# gpio_expander.net
KiCad netlist of a schematic drawn in Altium Designer
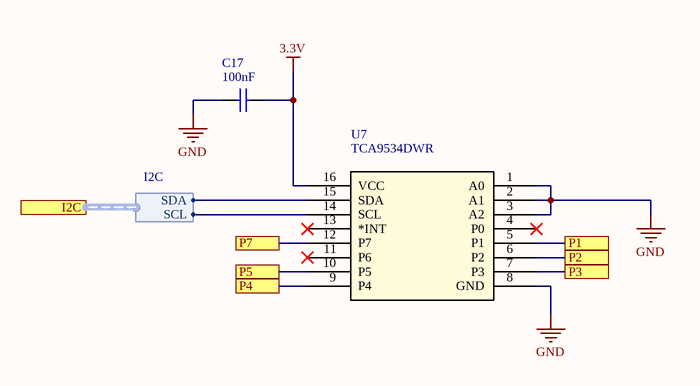
[diagram p0: gpio_expander.SchDoc]

(export (version "E")
  (design (tool "Eeschema 10.0.6"))
  (components
    (comp (ref "C17")
      (value "100nF")
      (footprint "0603 - Capacitor")
      (description "Nonpolarized Capacitor")
      (fields (field (name "Comment") "Capacitor - Nonpolarized"))
      (libsource (lib "General") (part "Capacitor - Nonpolarized"))
    )
    (comp (ref "U7")
      (value "TCA9534DWR")
      (footprint "TCA9534DWR")
      (fields (field (name "COPYRIGHT") "Copyright (C) 2022 Ultra Librarian. All rights reserved."))
      (libsource (lib "General") (part "TCA9534DWR"))
    )
  )
  (nets
    (net (code "2") (name "/P1") (class "Default")
      (node (ref "U7") (pin "5") (pinfunction "P1_5") (pintype "passive"))
    )
    (net (code "3") (name "/P2") (class "Default")
      (node (ref "U7") (pin "6") (pinfunction "P2_6") (pintype "passive"))
    )
    (net (code "4") (name "/P3") (class "Default")
      (node (ref "U7") (pin "7") (pinfunction "P3_7") (pintype "passive"))
    )
    (net (code "5") (name "/P4") (class "Default")
      (node (ref "U7") (pin "9") (pinfunction "P4_9") (pintype "passive"))
    )
    (net (code "6") (name "/P5") (class "Default")
      (node (ref "U7") (pin "10") (pinfunction "P5_10") (pintype "passive"))
    )
    (net (code "7") (name "/P7") (class "Default")
      (node (ref "U7") (pin "12") (pinfunction "P7_12") (pintype "passive"))
    )
    (net (code "8") (name "/SCL") (class "Default")
      (node (ref "U7") (pin "14") (pinfunction "SCL_14") (pintype "passive"))
    )
    (net (code "9") (name "/SDA") (class "Default")
      (node (ref "U7") (pin "15") (pinfunction "SDA_15") (pintype "passive"))
    )
    (net (code "11") (name "3.3V") (class "Default")
      (node (ref "C17") (pin "2") (pinfunction "2_2") (pintype "passive"))
      (node (ref "U7") (pin "16") (pinfunction "VCC_16") (pintype "power_in"))
    )
    (net (code "12") (name "GND") (class "Default")
      (node (ref "C17") (pin "1") (pinfunction "1_1") (pintype "passive"))
      (node (ref "U7") (pin "1") (pinfunction "A0_1") (pintype "passive"))
      (node (ref "U7") (pin "2") (pinfunction "A1_2") (pintype "passive"))
      (node (ref "U7") (pin "3") (pinfunction "A2_3") (pintype "passive"))
      (node (ref "U7") (pin "8") (pinfunction "GND_8") (pintype "power_in"))
    )
    (net (code "13") (name "unconnected-(U7-*INT-Pad13)") (class "Default")
      (node (ref "U7") (pin "13") (pinfunction "*INT_13") (pintype "passive+no_connect"))
    )
    (net (code "14") (name "unconnected-(U7-P0-Pad4)") (class "Default")
      (node (ref "U7") (pin "4") (pinfunction "P0_4") (pintype "passive+no_connect"))
    )
    (net (code "15") (name "unconnected-(U7-P6-Pad11)") (class "Default")
      (node (ref "U7") (pin "11") (pinfunction "P6_11") (pintype "passive+no_connect"))
    )
  )
)
